# Qwiic_Long_Distance-PCA9615.net
KiCad netlist of a schematic drawn in EAGLE
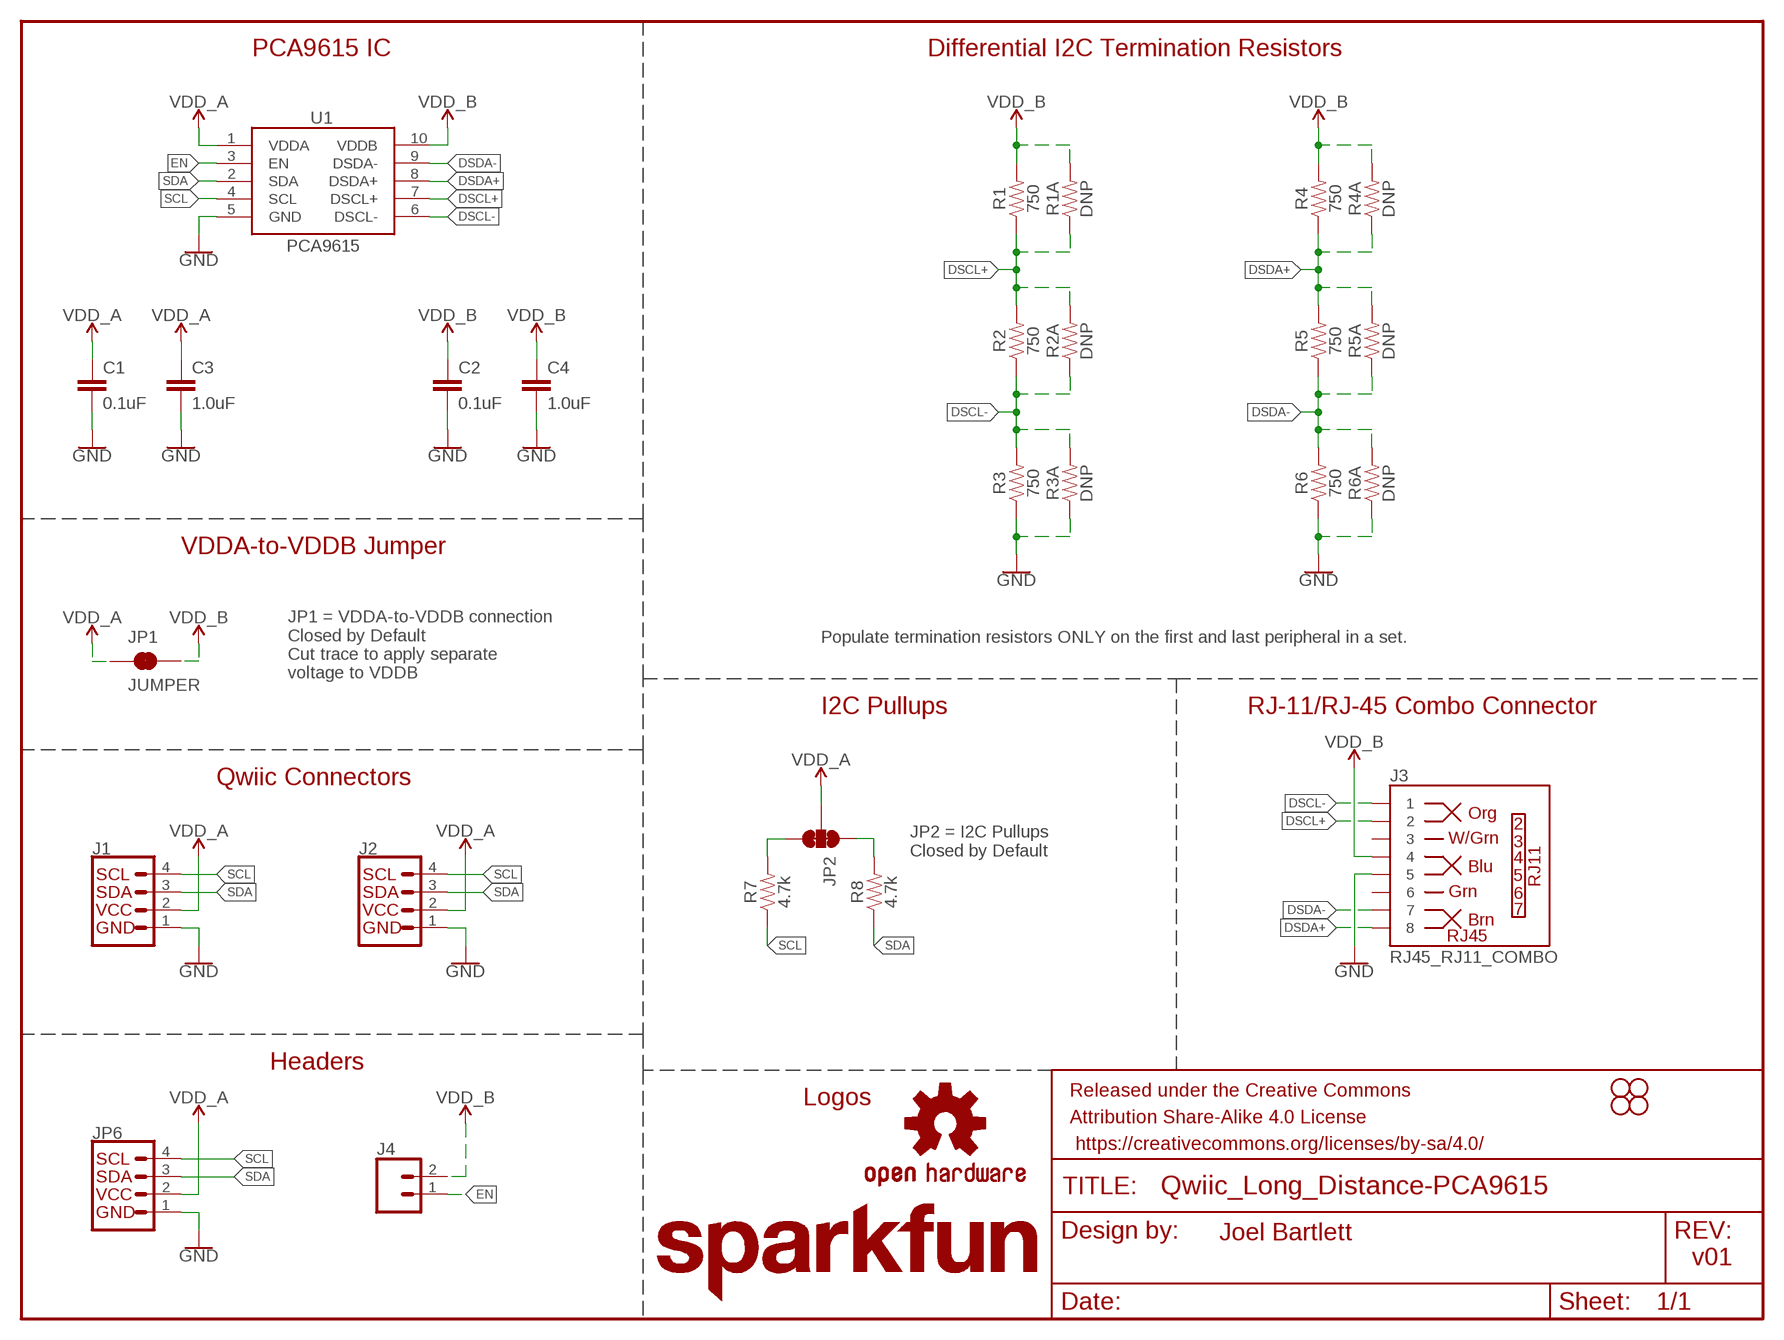
[diagram p0: schematic, sheet 1]

(export (version "E")
  (design (tool "Eeschema 10.0.6"))
  (components
    (comp (ref "C1")
      (value "0.1uF")
      (footprint "eagle-import:0603")
      (libsource (lib "eagle-import") (part "0.1UF-0603-25V-(+80/-20%)"))
    )
    (comp (ref "C2")
      (value "0.1uF")
      (footprint "eagle-import:0603")
      (libsource (lib "eagle-import") (part "0.1UF-0603-25V-(+80/-20%)"))
    )
    (comp (ref "C3")
      (value "1.0uF")
      (footprint "eagle-import:0603")
      (libsource (lib "eagle-import") (part "1.0UF-0603-16V-10%"))
    )
    (comp (ref "C4")
      (value "1.0uF")
      (footprint "eagle-import:0603")
      (libsource (lib "eagle-import") (part "1.0UF-0603-16V-10%"))
    )
    (comp (ref "FRAME1")
      (value "FRAME-LETTER")
      (footprint "eagle-import:CREATIVE_COMMONS")
      (libsource (lib "eagle-import") (part "FRAME-LETTER"))
    )
    (comp (ref "H1")
      (value "STAND-OFF")
      (footprint "eagle-import:STAND-OFF")
      (libsource (lib "eagle-import") (part "STAND-OFF"))
    )
    (comp (ref "H2")
      (value "STAND-OFF")
      (footprint "eagle-import:STAND-OFF")
      (libsource (lib "eagle-import") (part "STAND-OFF"))
    )
    (comp (ref "H3")
      (value "STAND-OFF")
      (footprint "eagle-import:STAND-OFF")
      (libsource (lib "eagle-import") (part "STAND-OFF"))
    )
    (comp (ref "H4")
      (value "STAND-OFF")
      (footprint "eagle-import:STAND-OFF")
      (libsource (lib "eagle-import") (part "STAND-OFF"))
    )
    (comp (ref "J1")
      (value "QWIIC_CONNECTORJS-1MM")
      (footprint "eagle-import:1X04_1MM_RA")
      (libsource (lib "eagle-import") (part "QWIIC_CONNECTORJS-1MM"))
    )
    (comp (ref "J2")
      (value "QWIIC_CONNECTORJS-1MM")
      (footprint "eagle-import:1X04_1MM_RA")
      (libsource (lib "eagle-import") (part "QWIIC_CONNECTORJS-1MM"))
    )
    (comp (ref "J3")
      (value "RJ45_RJ11_COMBO")
      (footprint "eagle-import:RJ45_RJ11_COMBO")
      (libsource (lib "eagle-import") (part "RJ45_RJ11_COMBO"))
    )
    (comp (ref "J4")
      (value "CONN_02")
      (footprint "eagle-import:1X02")
      (libsource (lib "eagle-import") (part "CONN_02"))
    )
    (comp (ref "JP1")
      (value "JUMPER")
      (footprint "eagle-import:SMT-JUMPER_2_NC_TRACE_SILK")
      (libsource (lib "eagle-import") (part "JUMPER-SMT_2_NC_TRACE_SILK"))
    )
    (comp (ref "JP2")
      (value "JUMPER-SMT_3_2-NC_TRACE_SILK")
      (footprint "eagle-import:SMT-JUMPER_3_2-NC_TRACE_SILK")
      (libsource (lib "eagle-import") (part "JUMPER-SMT_3_2-NC_TRACE_SILK"))
    )
    (comp (ref "JP6")
      (value "I2C_STANDARDSILK")
      (footprint "eagle-import:1X04")
      (libsource (lib "eagle-import") (part "I2C_STANDARDSILK"))
    )
    (comp (ref "LOGO1")
      (value "OSHW-LOGOM")
      (footprint "eagle-import:OSHW-LOGO-M")
      (libsource (lib "eagle-import") (part "OSHW-LOGOM"))
    )
    (comp (ref "LOGO2")
      (value "SFE_LOGO_NAME.1_INCH")
      (footprint "eagle-import:SFE_LOGO_NAME_.1")
      (libsource (lib "eagle-import") (part "SFE_LOGO_NAME.1_INCH"))
    )
    (comp (ref "R1")
      (value "750")
      (footprint "eagle-import:0603")
      (libsource (lib "eagle-import") (part "750OHM-0603-1/10W-1%"))
    )
    (comp (ref "R1A")
      (value "DNP")
      (footprint "eagle-import:AXIAL-0.3")
      (libsource (lib "eagle-import") (part "RESISTORAXIAL-0.3"))
    )
    (comp (ref "R2")
      (value "750")
      (footprint "eagle-import:0603")
      (libsource (lib "eagle-import") (part "750OHM-0603-1/10W-1%"))
    )
    (comp (ref "R2A")
      (value "DNP")
      (footprint "eagle-import:AXIAL-0.3")
      (libsource (lib "eagle-import") (part "RESISTORAXIAL-0.3"))
    )
    (comp (ref "R3")
      (value "750")
      (footprint "eagle-import:0603")
      (libsource (lib "eagle-import") (part "750OHM-0603-1/10W-1%"))
    )
    (comp (ref "R3A")
      (value "DNP")
      (footprint "eagle-import:AXIAL-0.3")
      (libsource (lib "eagle-import") (part "RESISTORAXIAL-0.3"))
    )
    (comp (ref "R4")
      (value "750")
      (footprint "eagle-import:0603")
      (libsource (lib "eagle-import") (part "750OHM-0603-1/10W-1%"))
    )
    (comp (ref "R4A")
      (value "DNP")
      (footprint "eagle-import:AXIAL-0.3")
      (libsource (lib "eagle-import") (part "RESISTORAXIAL-0.3"))
    )
    (comp (ref "R5")
      (value "750")
      (footprint "eagle-import:0603")
      (libsource (lib "eagle-import") (part "750OHM-0603-1/10W-1%"))
    )
    (comp (ref "R5A")
      (value "DNP")
      (footprint "eagle-import:AXIAL-0.3")
      (libsource (lib "eagle-import") (part "RESISTORAXIAL-0.3"))
    )
    (comp (ref "R6")
      (value "750")
      (footprint "eagle-import:0603")
      (libsource (lib "eagle-import") (part "750OHM-0603-1/10W-1%"))
    )
    (comp (ref "R6A")
      (value "DNP")
      (footprint "eagle-import:AXIAL-0.3")
      (libsource (lib "eagle-import") (part "RESISTORAXIAL-0.3"))
    )
    (comp (ref "R7")
      (value "4.7k")
      (footprint "eagle-import:0603")
      (libsource (lib "eagle-import") (part "4.7KOHM-0603-1/10W-1%"))
    )
    (comp (ref "R8")
      (value "4.7k")
      (footprint "eagle-import:0603")
      (libsource (lib "eagle-import") (part "4.7KOHM-0603-1/10W-1%"))
    )
    (comp (ref "U1")
      (value "PCA9615")
      (footprint "eagle-import:TSSOP10")
      (libsource (lib "eagle-import") (part "PCA9615"))
    )
  )
  (nets
    (net (code "1") (name "DSCL+") (class "Default")
      (node (ref "J3") (pin "2") (pinfunction "2_2") (pintype "bidirectional"))
      (node (ref "R1") (pin "1") (pinfunction "1_1") (pintype "passive"))
      (node (ref "R1A") (pin "P$1") (pinfunction "1_P$1") (pintype "passive"))
      (node (ref "R2") (pin "2") (pinfunction "2_2") (pintype "passive"))
      (node (ref "R2A") (pin "P$2") (pinfunction "2_P$2") (pintype "passive"))
      (node (ref "U1") (pin "7") (pinfunction "DSCL+_7") (pintype "bidirectional"))
    )
    (net (code "2") (name "DSCL-") (class "Default")
      (node (ref "J3") (pin "1") (pinfunction "1_1") (pintype "bidirectional"))
      (node (ref "R2") (pin "1") (pinfunction "1_1") (pintype "passive"))
      (node (ref "R2A") (pin "P$1") (pinfunction "1_P$1") (pintype "passive"))
      (node (ref "R3") (pin "2") (pinfunction "2_2") (pintype "passive"))
      (node (ref "R3A") (pin "P$2") (pinfunction "2_P$2") (pintype "passive"))
      (node (ref "U1") (pin "6") (pinfunction "DSCL-_6") (pintype "bidirectional"))
    )
    (net (code "3") (name "DSDA+") (class "Default")
      (node (ref "J3") (pin "8") (pinfunction "8_8") (pintype "bidirectional"))
      (node (ref "R4") (pin "1") (pinfunction "1_1") (pintype "passive"))
      (node (ref "R4A") (pin "P$1") (pinfunction "1_P$1") (pintype "passive"))
      (node (ref "R5") (pin "2") (pinfunction "2_2") (pintype "passive"))
      (node (ref "R5A") (pin "P$2") (pinfunction "2_P$2") (pintype "passive"))
      (node (ref "U1") (pin "8") (pinfunction "DSDA+_8") (pintype "bidirectional"))
    )
    (net (code "4") (name "DSDA-") (class "Default")
      (node (ref "J3") (pin "7") (pinfunction "7_7") (pintype "bidirectional"))
      (node (ref "R5") (pin "1") (pinfunction "1_1") (pintype "passive"))
      (node (ref "R5A") (pin "P$1") (pinfunction "1_P$1") (pintype "passive"))
      (node (ref "R6") (pin "2") (pinfunction "2_2") (pintype "passive"))
      (node (ref "R6A") (pin "P$2") (pinfunction "2_P$2") (pintype "passive"))
      (node (ref "U1") (pin "9") (pinfunction "DSDA-_9") (pintype "bidirectional"))
    )
    (net (code "5") (name "EN") (class "Default")
      (node (ref "J4") (pin "1") (pinfunction "1_1") (pintype "passive"))
      (node (ref "U1") (pin "3") (pinfunction "EN_3") (pintype "bidirectional"))
    )
    (net (code "6") (name "GND") (class "Default")
      (node (ref "C1") (pin "2") (pinfunction "2_2") (pintype "passive"))
      (node (ref "C2") (pin "2") (pinfunction "2_2") (pintype "passive"))
      (node (ref "C3") (pin "2") (pinfunction "2_2") (pintype "passive"))
      (node (ref "C4") (pin "2") (pinfunction "2_2") (pintype "passive"))
      (node (ref "J1") (pin "1") (pinfunction "1_1") (pintype "power_in"))
      (node (ref "J2") (pin "1") (pinfunction "1_1") (pintype "power_in"))
      (node (ref "J3") (pin "5") (pinfunction "5_5") (pintype "bidirectional"))
      (node (ref "JP6") (pin "1") (pinfunction "GND_1") (pintype "power_in"))
      (node (ref "R3") (pin "1") (pinfunction "1_1") (pintype "passive"))
      (node (ref "R3A") (pin "P$1") (pinfunction "1_P$1") (pintype "passive"))
      (node (ref "R6") (pin "1") (pinfunction "1_1") (pintype "passive"))
      (node (ref "R6A") (pin "P$1") (pinfunction "1_P$1") (pintype "passive"))
      (node (ref "U1") (pin "5") (pinfunction "GND_5") (pintype "bidirectional"))
    )
    (net (code "7") (name "Net-(JP2-Pad1)") (class "Default")
      (node (ref "JP2") (pin "1") (pinfunction "1_1") (pintype "passive"))
      (node (ref "R8") (pin "2") (pinfunction "2_2") (pintype "passive"))
    )
    (net (code "8") (name "Net-(JP2-Pad3)") (class "Default")
      (node (ref "JP2") (pin "3") (pinfunction "3_3") (pintype "passive"))
      (node (ref "R7") (pin "2") (pinfunction "2_2") (pintype "passive"))
    )
    (net (code "9") (name "SCL") (class "Default")
      (node (ref "J1") (pin "4") (pinfunction "4_4") (pintype "passive"))
      (node (ref "J2") (pin "4") (pinfunction "4_4") (pintype "passive"))
      (node (ref "JP6") (pin "4") (pinfunction "SCL_4") (pintype "passive"))
      (node (ref "R7") (pin "1") (pinfunction "1_1") (pintype "passive"))
      (node (ref "U1") (pin "4") (pinfunction "SCL_4") (pintype "bidirectional"))
    )
    (net (code "10") (name "SDA") (class "Default")
      (node (ref "J1") (pin "3") (pinfunction "3_3") (pintype "passive"))
      (node (ref "J2") (pin "3") (pinfunction "3_3") (pintype "passive"))
      (node (ref "JP6") (pin "3") (pinfunction "SDA_3") (pintype "passive"))
      (node (ref "R8") (pin "1") (pinfunction "1_1") (pintype "passive"))
      (node (ref "U1") (pin "2") (pinfunction "SDA_2") (pintype "bidirectional"))
    )
    (net (code "11") (name "VDD_A") (class "Default")
      (node (ref "C1") (pin "1") (pinfunction "1_1") (pintype "passive"))
      (node (ref "C3") (pin "1") (pinfunction "1_1") (pintype "passive"))
      (node (ref "J1") (pin "2") (pinfunction "2_2") (pintype "power_in"))
      (node (ref "J2") (pin "2") (pinfunction "2_2") (pintype "power_in"))
      (node (ref "JP1") (pin "1") (pinfunction "1_1") (pintype "passive"))
      (node (ref "JP2") (pin "2") (pinfunction "2_2") (pintype "passive"))
      (node (ref "JP6") (pin "2") (pinfunction "VCC_2") (pintype "power_in"))
      (node (ref "U1") (pin "1") (pinfunction "VDDA_1") (pintype "bidirectional"))
    )
    (net (code "12") (name "VDD_B") (class "Default")
      (node (ref "C2") (pin "1") (pinfunction "1_1") (pintype "passive"))
      (node (ref "C4") (pin "1") (pinfunction "1_1") (pintype "passive"))
      (node (ref "J3") (pin "4") (pinfunction "4_4") (pintype "bidirectional"))
      (node (ref "J4") (pin "2") (pinfunction "2_2") (pintype "passive"))
      (node (ref "JP1") (pin "2") (pinfunction "2_2") (pintype "passive"))
      (node (ref "R1") (pin "2") (pinfunction "2_2") (pintype "passive"))
      (node (ref "R1A") (pin "P$2") (pinfunction "2_P$2") (pintype "passive"))
      (node (ref "R4") (pin "2") (pinfunction "2_2") (pintype "passive"))
      (node (ref "R4A") (pin "P$2") (pinfunction "2_P$2") (pintype "passive"))
      (node (ref "U1") (pin "10") (pinfunction "VDDB_10") (pintype "bidirectional"))
    )
    (net (code "13") (name "unconnected-(J3-Pad3)") (class "Default")
      (node (ref "J3") (pin "3") (pinfunction "3_3") (pintype "bidirectional"))
    )
    (net (code "14") (name "unconnected-(J3-Pad6)") (class "Default")
      (node (ref "J3") (pin "6") (pinfunction "6_6") (pintype "bidirectional"))
    )
  )
)
